# 1-Schematic_GPIO_WAVER_18PIN.net
KiCad netlist of a schematic drawn in EasyEDA
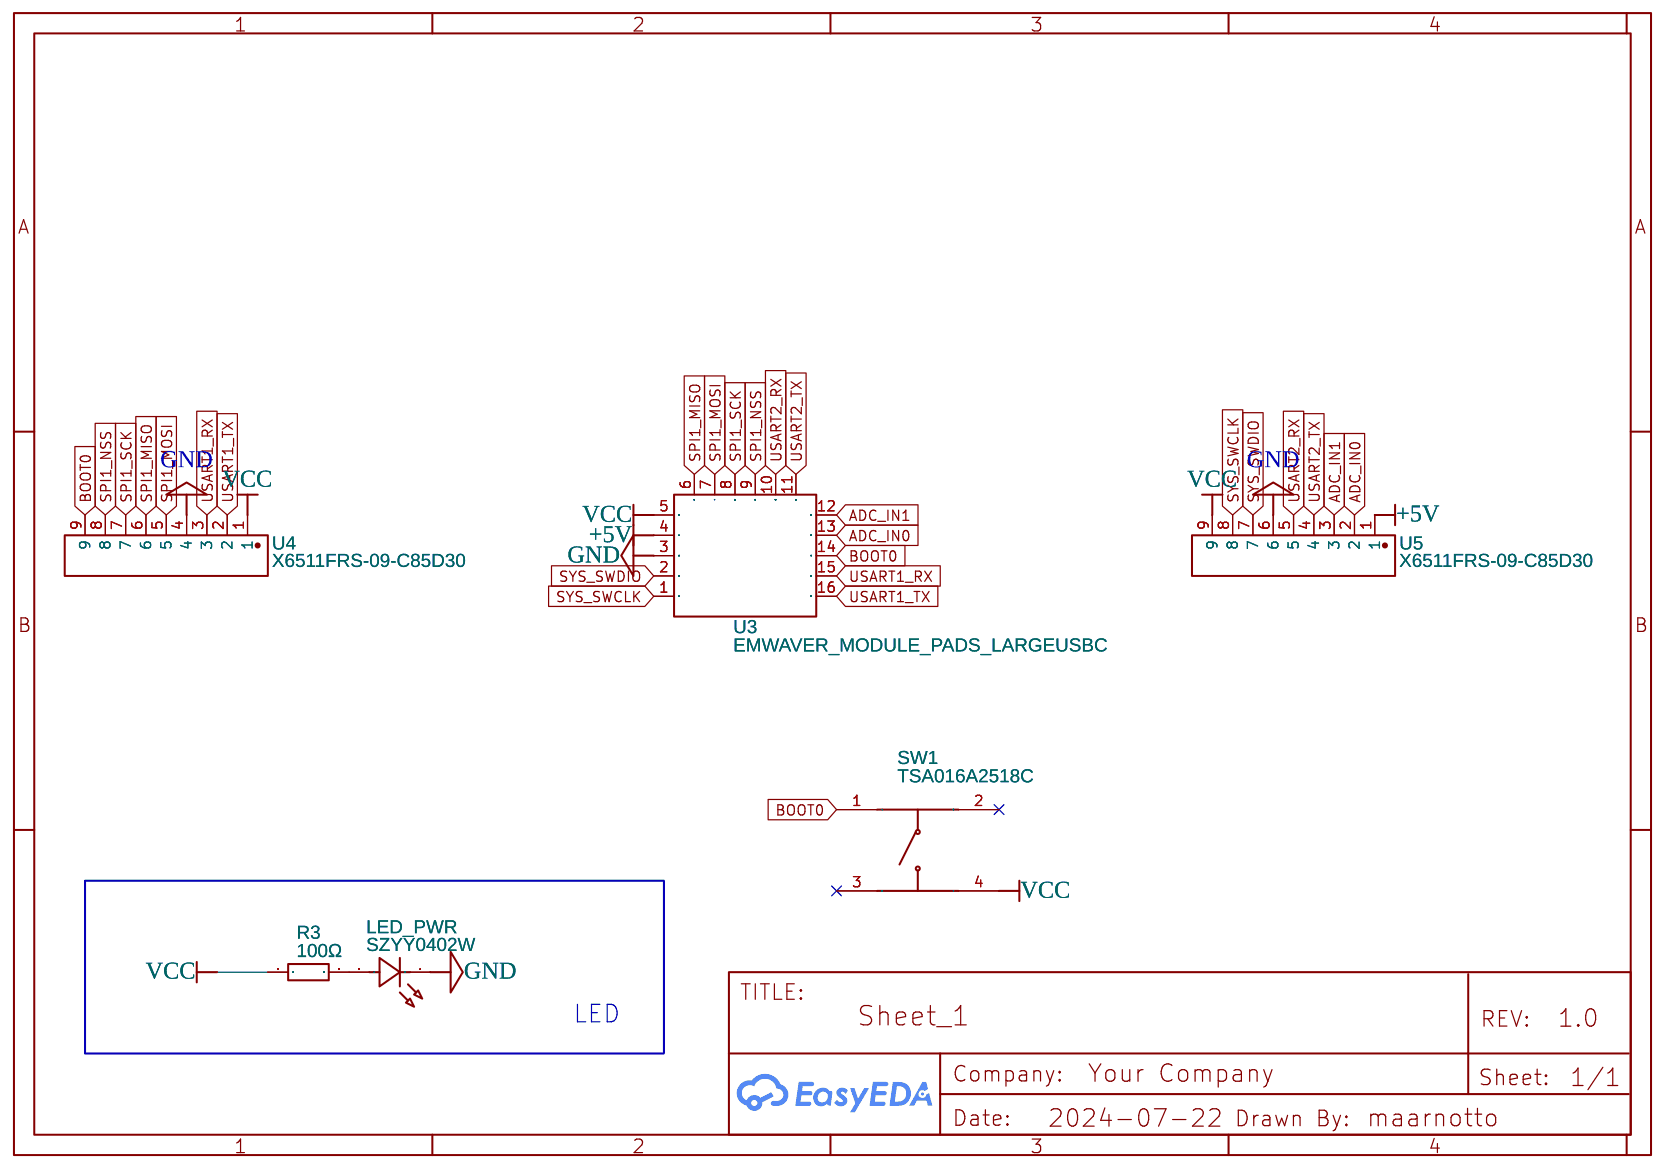
[diagram p0: schematic sheet]

(export (version "E")
  (design (tool "Eeschema 10.0.6"))
  (components
    (comp (ref "LED_PWR")
      (value "SZYY0402W")
      (fields (field (name "Manufacturer") "yongyu(永裕光电)"))
      (libsource (lib "") (part "SZYY0402W"))
    )
    (comp (ref "R3")
      (value "100Ω")
      (fields
        (field (name "Manufacturer Part") "0402WGF1000TCE")
        (field (name "Manufacturer") "UNI-ROYAL(厚声)")
      )
      (libsource (lib "") (part "0402WGF1000TCE"))
    )
    (comp (ref "SW1")
      (value "TSA016A2518C")
      (fields (field (name "Manufacturer") "BZCN(博众电气)"))
      (libsource (lib "") (part "TSA016A2518C"))
    )
    (comp (ref "U3")
      (value "EMWAVER_MODULE_PADS_LARGEUSBC")
      (libsource (lib "") (part "EMWAVER_MODULE_PADS_LARGEUSBC"))
    )
    (comp (ref "U4")
      (value "X6511FRS-09-C85D30")
      (fields (field (name "Manufacturer") "XKB Connectivity(中国星坤)"))
      (libsource (lib "") (part "X6511FRS-09-C85D30"))
    )
    (comp (ref "U5")
      (value "X6511FRS-09-C85D30")
      (fields (field (name "Manufacturer") "XKB Connectivity(中国星坤)"))
      (libsource (lib "") (part "X6511FRS-09-C85D30"))
    )
  )
  (nets
    (net (code "1") (name "+5V") (class "Default")
      (node (ref "U3") (pin "4") (pinfunction "4_4") (pintype "unspecified"))
      (node (ref "U5") (pin "1") (pinfunction "1_1") (pintype "unspecified"))
    )
    (net (code "2") (name "ADC_IN0") (class "Default")
      (node (ref "U3") (pin "13") (pinfunction "13_13") (pintype "unspecified"))
      (node (ref "U5") (pin "2") (pinfunction "2_2") (pintype "unspecified"))
    )
    (net (code "3") (name "ADC_IN1") (class "Default")
      (node (ref "U3") (pin "12") (pinfunction "12_12") (pintype "unspecified"))
      (node (ref "U5") (pin "3") (pinfunction "3_3") (pintype "unspecified"))
    )
    (net (code "4") (name "BOOT0") (class "Default")
      (node (ref "SW1") (pin "1") (pinfunction "1_1") (pintype "unspecified"))
      (node (ref "U3") (pin "14") (pinfunction "14_14") (pintype "unspecified"))
      (node (ref "U4") (pin "9") (pinfunction "9_9") (pintype "unspecified"))
    )
    (net (code "5") (name "GND") (class "Default")
      (node (ref "LED_PWR") (pin "1") (pinfunction "K_1") (pintype "unspecified"))
      (node (ref "U3") (pin "3") (pinfunction "3_3") (pintype "unspecified"))
      (node (ref "U4") (pin "4") (pinfunction "4_4") (pintype "unspecified"))
      (node (ref "U5") (pin "6") (pinfunction "6_6") (pintype "unspecified"))
    )
    (net (code "6") (name "Net-(LED_PWR-A)") (class "Default")
      (node (ref "LED_PWR") (pin "2") (pinfunction "A_2") (pintype "unspecified"))
      (node (ref "R3") (pin "2") (pinfunction "2_2") (pintype "input"))
    )
    (net (code "7") (name "SPI1_MISO") (class "Default")
      (node (ref "U3") (pin "6") (pinfunction "6_6") (pintype "unspecified"))
      (node (ref "U4") (pin "6") (pinfunction "6_6") (pintype "unspecified"))
    )
    (net (code "8") (name "SPI1_MOSI") (class "Default")
      (node (ref "U3") (pin "7") (pinfunction "7_7") (pintype "unspecified"))
      (node (ref "U4") (pin "5") (pinfunction "5_5") (pintype "unspecified"))
    )
    (net (code "9") (name "SPI1_NSS") (class "Default")
      (node (ref "U3") (pin "9") (pinfunction "9_9") (pintype "unspecified"))
      (node (ref "U4") (pin "8") (pinfunction "8_8") (pintype "unspecified"))
    )
    (net (code "10") (name "SPI1_SCK") (class "Default")
      (node (ref "U3") (pin "8") (pinfunction "8_8") (pintype "unspecified"))
      (node (ref "U4") (pin "7") (pinfunction "7_7") (pintype "unspecified"))
    )
    (net (code "11") (name "SYS_SWCLK") (class "Default")
      (node (ref "U3") (pin "1") (pinfunction "1_1") (pintype "unspecified"))
      (node (ref "U5") (pin "8") (pinfunction "8_8") (pintype "unspecified"))
    )
    (net (code "12") (name "SYS_SWDIO") (class "Default")
      (node (ref "U3") (pin "2") (pinfunction "2_2") (pintype "unspecified"))
      (node (ref "U5") (pin "7") (pinfunction "7_7") (pintype "unspecified"))
    )
    (net (code "13") (name "USART1_RX") (class "Default")
      (node (ref "U3") (pin "15") (pinfunction "15_15") (pintype "unspecified"))
      (node (ref "U4") (pin "3") (pinfunction "3_3") (pintype "unspecified"))
    )
    (net (code "14") (name "USART1_TX") (class "Default")
      (node (ref "U3") (pin "16") (pinfunction "16_16") (pintype "unspecified"))
      (node (ref "U4") (pin "2") (pinfunction "2_2") (pintype "unspecified"))
    )
    (net (code "15") (name "USART2_RX") (class "Default")
      (node (ref "U3") (pin "10") (pinfunction "10_10") (pintype "unspecified"))
      (node (ref "U5") (pin "5") (pinfunction "5_5") (pintype "unspecified"))
    )
    (net (code "16") (name "USART2_TX") (class "Default")
      (node (ref "U3") (pin "11") (pinfunction "11_11") (pintype "unspecified"))
      (node (ref "U5") (pin "4") (pinfunction "4_4") (pintype "unspecified"))
    )
    (net (code "17") (name "VCC") (class "Default")
      (node (ref "R3") (pin "1") (pinfunction "1_1") (pintype "input"))
      (node (ref "SW1") (pin "4") (pinfunction "4_4") (pintype "unspecified"))
      (node (ref "U3") (pin "5") (pinfunction "5_5") (pintype "unspecified"))
      (node (ref "U4") (pin "1") (pinfunction "1_1") (pintype "unspecified"))
      (node (ref "U5") (pin "9") (pinfunction "9_9") (pintype "unspecified"))
    )
    (net (code "18") (name "unconnected-(SW1-Pad2)") (class "Default")
      (node (ref "SW1") (pin "2") (pinfunction "2_2") (pintype "unspecified+no_connect"))
    )
    (net (code "19") (name "unconnected-(SW1-Pad3)") (class "Default")
      (node (ref "SW1") (pin "3") (pinfunction "3_3") (pintype "unspecified+no_connect"))
    )
  )
)
